# Processor_Interface.net
KiCad netlist of a schematic drawn in EAGLE
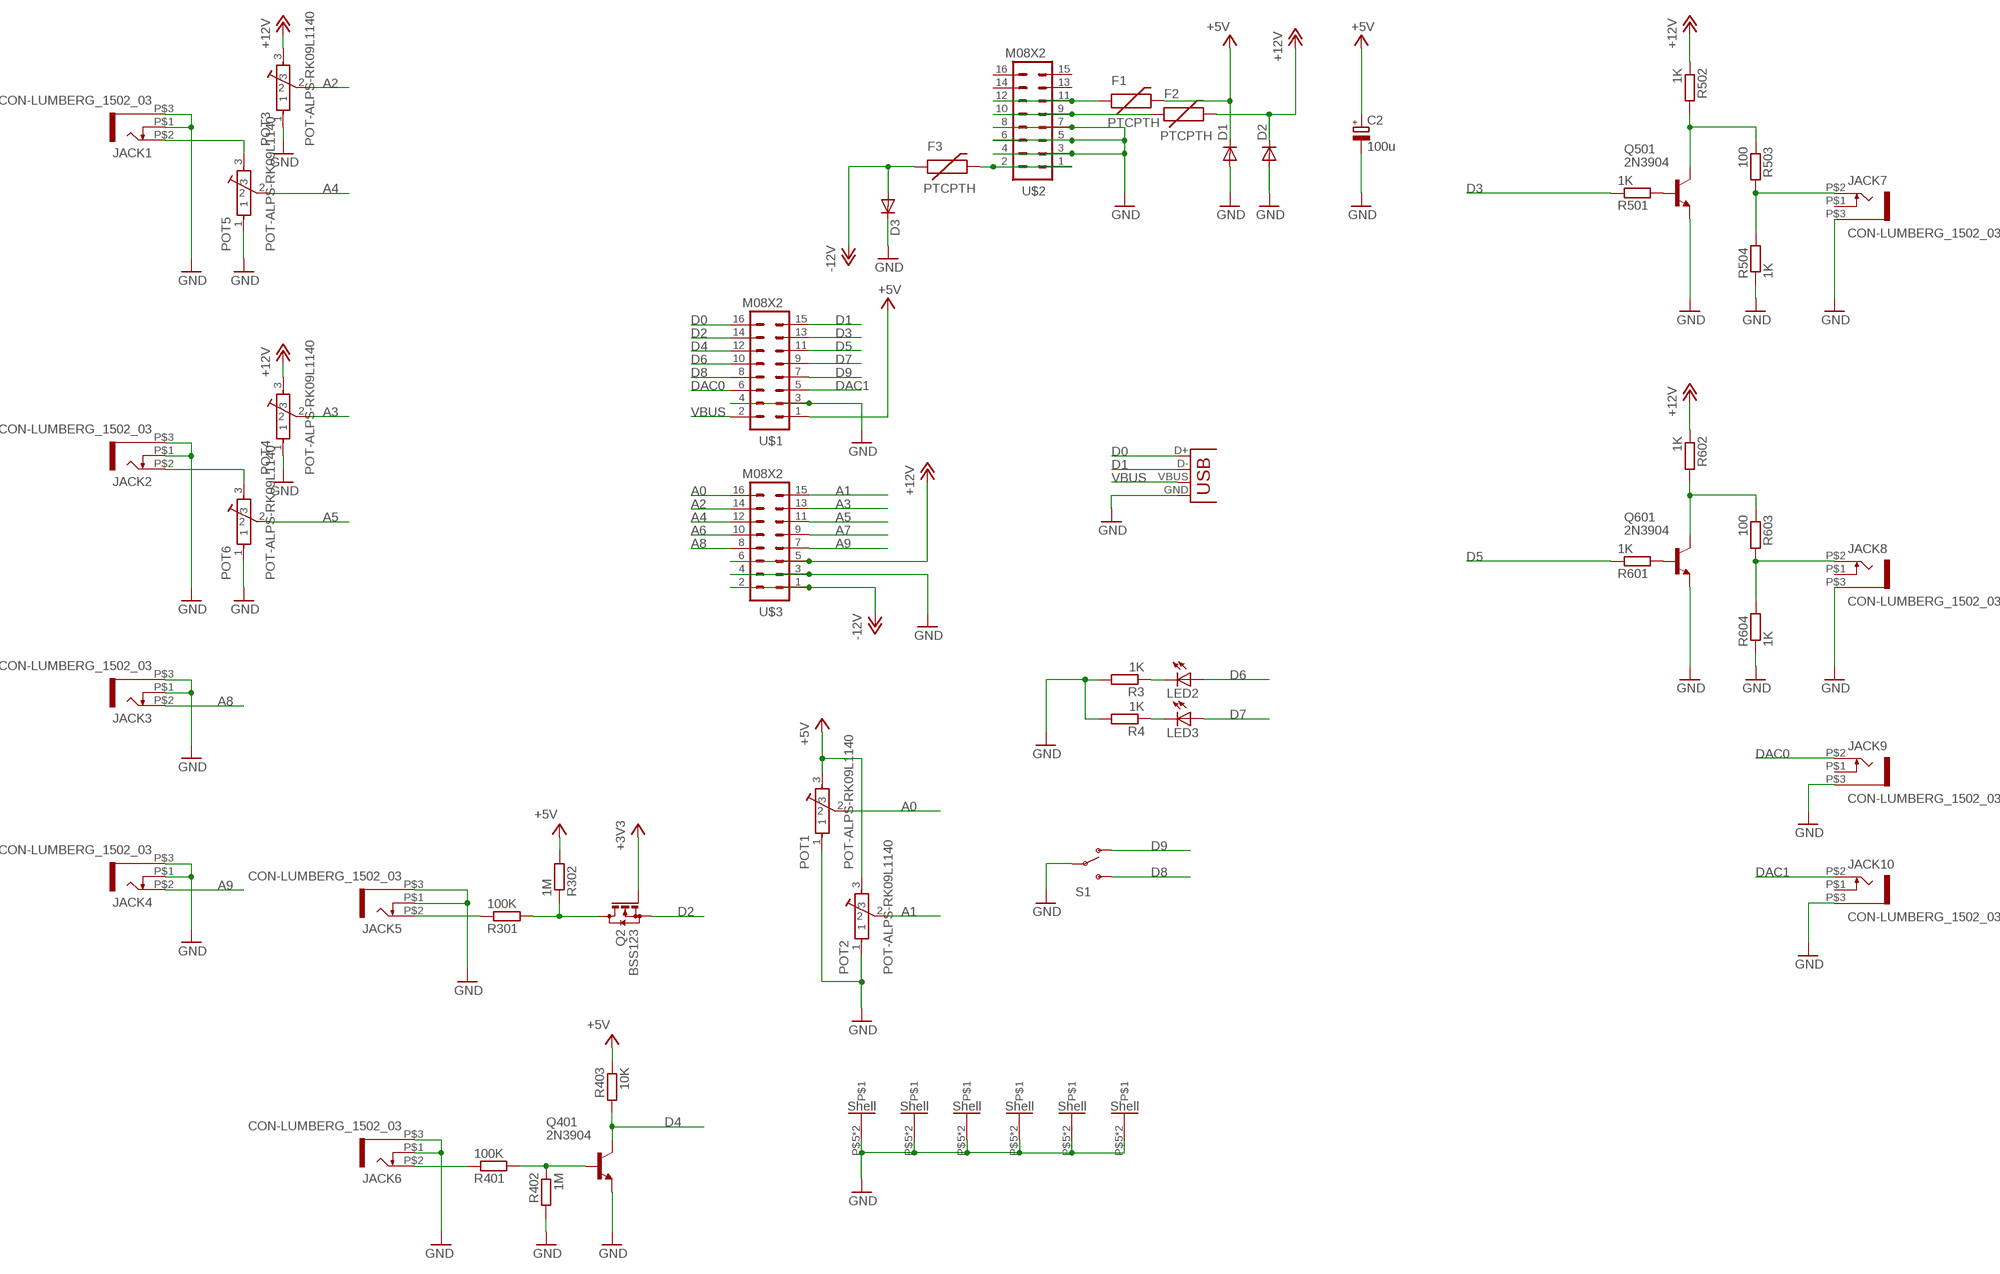
[diagram p0: schematic, sheet 1]

(export (version "E")
  (design (tool "Eeschema 10.0.6"))
  (components
    (comp (ref "C2")
      (value "100u")
      (footprint "eagle-import:E5-6")
      (libsource (lib "eagle-import") (part "CPOL-EUE5-6"))
    )
    (comp (ref "D1")
      (value "DIODEPTH")
      (footprint "eagle-import:DIODE-1N4001")
      (libsource (lib "eagle-import") (part "DIODEPTH"))
    )
    (comp (ref "D2")
      (value "DIODEPTH")
      (footprint "eagle-import:DIODE-1N4001")
      (libsource (lib "eagle-import") (part "DIODEPTH"))
    )
    (comp (ref "D3")
      (value "DIODEPTH")
      (footprint "eagle-import:DIODE-1N4001")
      (libsource (lib "eagle-import") (part "DIODEPTH"))
    )
    (comp (ref "F1")
      (value "PTCPTH")
      (footprint "eagle-import:PTC")
      (libsource (lib "eagle-import") (part "PTCPTH"))
    )
    (comp (ref "F2")
      (value "PTCPTH")
      (footprint "eagle-import:PTC")
      (libsource (lib "eagle-import") (part "PTCPTH"))
    )
    (comp (ref "F3")
      (value "PTCPTH")
      (footprint "eagle-import:PTC")
      (libsource (lib "eagle-import") (part "PTCPTH"))
    )
    (comp (ref "JACK1")
      (value "CON-LUMBERG_1502_03")
      (footprint "eagle-import:CON-LUMBERG_1502_03")
      (libsource (lib "eagle-import") (part "CON-LUMBERG_1502_03"))
    )
    (comp (ref "JACK2")
      (value "CON-LUMBERG_1502_03")
      (footprint "eagle-import:CON-LUMBERG_1502_03")
      (libsource (lib "eagle-import") (part "CON-LUMBERG_1502_03"))
    )
    (comp (ref "JACK3")
      (value "CON-LUMBERG_1502_03")
      (footprint "eagle-import:CON-LUMBERG_1502_03")
      (libsource (lib "eagle-import") (part "CON-LUMBERG_1502_03"))
    )
    (comp (ref "JACK4")
      (value "CON-LUMBERG_1502_03")
      (footprint "eagle-import:CON-LUMBERG_1502_03")
      (libsource (lib "eagle-import") (part "CON-LUMBERG_1502_03"))
    )
    (comp (ref "JACK5")
      (value "CON-LUMBERG_1502_03")
      (footprint "eagle-import:CON-LUMBERG_1502_03")
      (libsource (lib "eagle-import") (part "CON-LUMBERG_1502_03"))
    )
    (comp (ref "JACK6")
      (value "CON-LUMBERG_1502_03")
      (footprint "eagle-import:CON-LUMBERG_1502_03")
      (libsource (lib "eagle-import") (part "CON-LUMBERG_1502_03"))
    )
    (comp (ref "JACK7")
      (value "CON-LUMBERG_1502_03")
      (footprint "eagle-import:CON-LUMBERG_1502_03")
      (libsource (lib "eagle-import") (part "CON-LUMBERG_1502_03"))
    )
    (comp (ref "JACK8")
      (value "CON-LUMBERG_1502_03")
      (footprint "eagle-import:CON-LUMBERG_1502_03")
      (libsource (lib "eagle-import") (part "CON-LUMBERG_1502_03"))
    )
    (comp (ref "JACK9")
      (value "CON-LUMBERG_1502_03")
      (footprint "eagle-import:CON-LUMBERG_1502_03")
      (libsource (lib "eagle-import") (part "CON-LUMBERG_1502_03"))
    )
    (comp (ref "JACK10")
      (value "CON-LUMBERG_1502_03")
      (footprint "eagle-import:CON-LUMBERG_1502_03")
      (libsource (lib "eagle-import") (part "CON-LUMBERG_1502_03"))
    )
    (comp (ref "LED2")
      (value "LED3MM")
      (footprint "eagle-import:LED3MM")
      (libsource (lib "eagle-import") (part "LED3MM"))
    )
    (comp (ref "LED3")
      (value "LED3MM")
      (footprint "eagle-import:LED3MM")
      (libsource (lib "eagle-import") (part "LED3MM"))
    )
    (comp (ref "POT1")
      (value "POT-ALPS-RK09L1140")
      (footprint "eagle-import:POT-ALPS-RK09L1140")
      (libsource (lib "eagle-import") (part "POT-ALPS-RK09L1140"))
    )
    (comp (ref "POT2")
      (value "POT-ALPS-RK09L1140")
      (footprint "eagle-import:POT-ALPS-RK09L1140")
      (libsource (lib "eagle-import") (part "POT-ALPS-RK09L1140"))
    )
    (comp (ref "POT3")
      (value "POT-ALPS-RK09L1140")
      (footprint "eagle-import:POT-ALPS-RK09L1140")
      (libsource (lib "eagle-import") (part "POT-ALPS-RK09L1140"))
    )
    (comp (ref "POT4")
      (value "POT-ALPS-RK09L1140")
      (footprint "eagle-import:POT-ALPS-RK09L1140")
      (libsource (lib "eagle-import") (part "POT-ALPS-RK09L1140"))
    )
    (comp (ref "POT5")
      (value "POT-ALPS-RK09L1140")
      (footprint "eagle-import:POT-ALPS-RK09L1140")
      (libsource (lib "eagle-import") (part "POT-ALPS-RK09L1140"))
    )
    (comp (ref "POT6")
      (value "POT-ALPS-RK09L1140")
      (footprint "eagle-import:POT-ALPS-RK09L1140")
      (libsource (lib "eagle-import") (part "POT-ALPS-RK09L1140"))
    )
    (comp (ref "Q2")
      (value "BSS123")
      (footprint "eagle-import:SOT23")
      (libsource (lib "eagle-import") (part "BSS123"))
    )
    (comp (ref "Q401")
      (value "2N3904")
      (footprint "eagle-import:TO92")
      (libsource (lib "eagle-import") (part "2N3904"))
    )
    (comp (ref "Q501")
      (value "2N3904")
      (footprint "eagle-import:TO92")
      (libsource (lib "eagle-import") (part "2N3904"))
    )
    (comp (ref "Q601")
      (value "2N3904")
      (footprint "eagle-import:TO92")
      (libsource (lib "eagle-import") (part "2N3904"))
    )
    (comp (ref "R3")
      (value "1K")
      (footprint "eagle-import:0204_7")
      (libsource (lib "eagle-import") (part "R-EU_0204/7"))
    )
    (comp (ref "R4")
      (value "1K")
      (footprint "eagle-import:0204_7")
      (libsource (lib "eagle-import") (part "R-EU_0204/7"))
    )
    (comp (ref "R301")
      (value "100K")
      (footprint "eagle-import:0204_7")
      (libsource (lib "eagle-import") (part "R-EU_0204/7"))
    )
    (comp (ref "R302")
      (value "1M")
      (footprint "eagle-import:0204_7")
      (libsource (lib "eagle-import") (part "R-EU_0204/7"))
    )
    (comp (ref "R401")
      (value "100K")
      (footprint "eagle-import:0204_7")
      (libsource (lib "eagle-import") (part "R-EU_0204/7"))
    )
    (comp (ref "R402")
      (value "1M")
      (footprint "eagle-import:0204_7")
      (libsource (lib "eagle-import") (part "R-EU_0204/7"))
    )
    (comp (ref "R403")
      (value "10K")
      (footprint "eagle-import:0204_7")
      (libsource (lib "eagle-import") (part "R-EU_0204/7"))
    )
    (comp (ref "R501")
      (value "1K")
      (footprint "eagle-import:0204_7")
      (libsource (lib "eagle-import") (part "R-EU_0204/7"))
    )
    (comp (ref "R502")
      (value "1K")
      (footprint "eagle-import:0204_7")
      (libsource (lib "eagle-import") (part "R-EU_0204/7"))
    )
    (comp (ref "R503")
      (value "100")
      (footprint "eagle-import:0204_7")
      (libsource (lib "eagle-import") (part "R-EU_0204/7"))
    )
    (comp (ref "R504")
      (value "1K")
      (footprint "eagle-import:0204_7")
      (libsource (lib "eagle-import") (part "R-EU_0204/7"))
    )
    (comp (ref "R601")
      (value "1K")
      (footprint "eagle-import:0204_7")
      (libsource (lib "eagle-import") (part "R-EU_0204/7"))
    )
    (comp (ref "R602")
      (value "1K")
      (footprint "eagle-import:0204_7")
      (libsource (lib "eagle-import") (part "R-EU_0204/7"))
    )
    (comp (ref "R603")
      (value "100")
      (footprint "eagle-import:0204_7")
      (libsource (lib "eagle-import") (part "R-EU_0204/7"))
    )
    (comp (ref "R604")
      (value "1K")
      (footprint "eagle-import:0204_7")
      (libsource (lib "eagle-import") (part "R-EU_0204/7"))
    )
    (comp (ref "S1")
      (value "SWITCH-SPST")
      (footprint "eagle-import:SWITCH-SPDT-SALECOM-T8014")
      (libsource (lib "eagle-import") (part "SWITCH-SPST"))
    )
    (comp (ref "U$1")
      (value "M08X2")
      (footprint "eagle-import:2X8")
      (libsource (lib "eagle-import") (part "M08X2"))
    )
    (comp (ref "U$2")
      (value "M08X2")
      (footprint "eagle-import:2X8")
      (libsource (lib "eagle-import") (part "M08X2"))
    )
    (comp (ref "U$3")
      (value "M08X2")
      (footprint "eagle-import:2X8")
      (libsource (lib "eagle-import") (part "M08X2"))
    )
    (comp (ref "X1")
      (value "USBPTH-VERTICAL")
      (footprint "eagle-import:USB-B-PTH-VERTICAL")
      (libsource (lib "eagle-import") (part "USBPTH-VERTICAL"))
    )
  )
  (nets
    (net (code "1") (name "+3V3") (class "Default")
      (node (ref "Q2") (pin "1") (pinfunction "G_1") (pintype "passive"))
    )
    (net (code "2") (name "+5V") (class "Default")
      (node (ref "C2") (pin "+") (pinfunction "+_+") (pintype "passive"))
      (node (ref "D1") (pin "C") (pinfunction "C_C") (pintype "passive"))
      (node (ref "F1") (pin "P$2") (pinfunction "2_P$2") (pintype "bidirectional"))
      (node (ref "POT1") (pin "3") (pinfunction "3_3") (pintype "bidirectional"))
      (node (ref "POT2") (pin "3") (pinfunction "3_3") (pintype "bidirectional"))
      (node (ref "R302") (pin "2") (pinfunction "2_2") (pintype "passive"))
      (node (ref "R403") (pin "1") (pinfunction "1_1") (pintype "passive"))
      (node (ref "U$1") (pin "1") (pinfunction "1_1") (pintype "passive"))
    )
    (net (code "3") (name "+12V") (class "Default")
      (node (ref "D2") (pin "C") (pinfunction "C_C") (pintype "passive"))
      (node (ref "F2") (pin "P$2") (pinfunction "2_P$2") (pintype "bidirectional"))
      (node (ref "POT3") (pin "3") (pinfunction "3_3") (pintype "bidirectional"))
      (node (ref "POT4") (pin "3") (pinfunction "3_3") (pintype "bidirectional"))
      (node (ref "R502") (pin "1") (pinfunction "1_1") (pintype "passive"))
      (node (ref "R602") (pin "1") (pinfunction "1_1") (pintype "passive"))
      (node (ref "U$3") (pin "5") (pinfunction "5_5") (pintype "passive"))
      (node (ref "U$3") (pin "6") (pinfunction "6_6") (pintype "passive"))
    )
    (net (code "4") (name "-12V") (class "Default")
      (node (ref "D3") (pin "A") (pinfunction "A_A") (pintype "passive"))
      (node (ref "F3") (pin "P$1") (pinfunction "1_P$1") (pintype "bidirectional"))
      (node (ref "U$3") (pin "1") (pinfunction "1_1") (pintype "passive"))
      (node (ref "U$3") (pin "2") (pinfunction "2_2") (pintype "passive"))
    )
    (net (code "5") (name "/A0") (class "Default")
      (node (ref "POT1") (pin "2") (pinfunction "2_2") (pintype "bidirectional"))
      (node (ref "U$3") (pin "16") (pinfunction "16_16") (pintype "passive"))
    )
    (net (code "6") (name "/A1") (class "Default")
      (node (ref "POT2") (pin "2") (pinfunction "2_2") (pintype "bidirectional"))
      (node (ref "U$3") (pin "15") (pinfunction "15_15") (pintype "passive"))
    )
    (net (code "7") (name "/A2") (class "Default")
      (node (ref "POT3") (pin "2") (pinfunction "2_2") (pintype "bidirectional"))
      (node (ref "U$3") (pin "14") (pinfunction "14_14") (pintype "passive"))
    )
    (net (code "8") (name "/A3") (class "Default")
      (node (ref "POT4") (pin "2") (pinfunction "2_2") (pintype "bidirectional"))
      (node (ref "U$3") (pin "13") (pinfunction "13_13") (pintype "passive"))
    )
    (net (code "9") (name "/A4") (class "Default")
      (node (ref "POT5") (pin "2") (pinfunction "2_2") (pintype "bidirectional"))
      (node (ref "U$3") (pin "12") (pinfunction "12_12") (pintype "passive"))
    )
    (net (code "10") (name "/A5") (class "Default")
      (node (ref "POT6") (pin "2") (pinfunction "2_2") (pintype "bidirectional"))
      (node (ref "U$3") (pin "11") (pinfunction "11_11") (pintype "passive"))
    )
    (net (code "11") (name "/A6") (class "Default")
      (node (ref "U$3") (pin "10") (pinfunction "10_10") (pintype "passive"))
    )
    (net (code "12") (name "/A7") (class "Default")
      (node (ref "U$3") (pin "9") (pinfunction "9_9") (pintype "passive"))
    )
    (net (code "13") (name "/A8") (class "Default")
      (node (ref "JACK3") (pin "P$2") (pinfunction "3_P$2") (pintype "passive"))
      (node (ref "U$3") (pin "8") (pinfunction "8_8") (pintype "passive"))
    )
    (net (code "14") (name "/A9") (class "Default")
      (node (ref "JACK4") (pin "P$2") (pinfunction "3_P$2") (pintype "passive"))
      (node (ref "U$3") (pin "7") (pinfunction "7_7") (pintype "passive"))
    )
    (net (code "15") (name "/D0") (class "Default")
      (node (ref "U$1") (pin "16") (pinfunction "16_16") (pintype "passive"))
      (node (ref "X1") (pin "D+") (pinfunction "D+_D+") (pintype "bidirectional"))
    )
    (net (code "16") (name "/D1") (class "Default")
      (node (ref "U$1") (pin "15") (pinfunction "15_15") (pintype "passive"))
      (node (ref "X1") (pin "D-") (pinfunction "D-_D-") (pintype "bidirectional"))
    )
    (net (code "17") (name "/D2") (class "Default")
      (node (ref "Q2") (pin "2") (pinfunction "S_2") (pintype "passive"))
      (node (ref "U$1") (pin "14") (pinfunction "14_14") (pintype "passive"))
    )
    (net (code "18") (name "/D3") (class "Default")
      (node (ref "R501") (pin "1") (pinfunction "1_1") (pintype "passive"))
      (node (ref "U$1") (pin "13") (pinfunction "13_13") (pintype "passive"))
    )
    (net (code "19") (name "/D4") (class "Default")
      (node (ref "Q401") (pin "1") (pinfunction "C_1") (pintype "passive"))
      (node (ref "R403") (pin "2") (pinfunction "2_2") (pintype "passive"))
      (node (ref "U$1") (pin "12") (pinfunction "12_12") (pintype "passive"))
    )
    (net (code "20") (name "/D5") (class "Default")
      (node (ref "R601") (pin "1") (pinfunction "1_1") (pintype "passive"))
      (node (ref "U$1") (pin "11") (pinfunction "11_11") (pintype "passive"))
    )
    (net (code "21") (name "/D6") (class "Default")
      (node (ref "LED2") (pin "A") (pinfunction "A_A") (pintype "passive"))
      (node (ref "U$1") (pin "10") (pinfunction "10_10") (pintype "passive"))
    )
    (net (code "22") (name "/D7") (class "Default")
      (node (ref "LED3") (pin "A") (pinfunction "A_A") (pintype "passive"))
      (node (ref "U$1") (pin "9") (pinfunction "9_9") (pintype "passive"))
    )
    (net (code "23") (name "/D8") (class "Default")
      (node (ref "S1") (pin "3") (pinfunction "S_3") (pintype "passive"))
      (node (ref "U$1") (pin "8") (pinfunction "8_8") (pintype "passive"))
    )
    (net (code "24") (name "/D9") (class "Default")
      (node (ref "S1") (pin "1") (pinfunction "O_1") (pintype "passive"))
      (node (ref "U$1") (pin "7") (pinfunction "7_7") (pintype "passive"))
    )
    (net (code "25") (name "/DAC0") (class "Default")
      (node (ref "JACK9") (pin "P$2") (pinfunction "3_P$2") (pintype "passive"))
      (node (ref "U$1") (pin "6") (pinfunction "6_6") (pintype "passive"))
    )
    (net (code "26") (name "/DAC1") (class "Default")
      (node (ref "JACK10") (pin "P$2") (pinfunction "3_P$2") (pintype "passive"))
      (node (ref "U$1") (pin "5") (pinfunction "5_5") (pintype "passive"))
    )
    (net (code "27") (name "/VBUS") (class "Default")
      (node (ref "U$1") (pin "2") (pinfunction "2_2") (pintype "passive"))
      (node (ref "X1") (pin "VBUS") (pinfunction "VBUS_VBUS") (pintype "bidirectional"))
    )
    (net (code "28") (name "GND") (class "Default")
      (node (ref "C2") (pin "-") (pinfunction "-_-") (pintype "passive"))
      (node (ref "D1") (pin "A") (pinfunction "A_A") (pintype "passive"))
      (node (ref "D2") (pin "A") (pinfunction "A_A") (pintype "passive"))
      (node (ref "D3") (pin "C") (pinfunction "C_C") (pintype "passive"))
      (node (ref "JACK1") (pin "P$1") (pinfunction "4_P$1") (pintype "passive"))
      (node (ref "JACK1") (pin "P$3") (pinfunction "5_P$3") (pintype "passive"))
      (node (ref "JACK10") (pin "P$3") (pinfunction "5_P$3") (pintype "passive"))
      (node (ref "JACK2") (pin "P$1") (pinfunction "4_P$1") (pintype "passive"))
      (node (ref "JACK2") (pin "P$3") (pinfunction "5_P$3") (pintype "passive"))
      (node (ref "JACK3") (pin "P$1") (pinfunction "4_P$1") (pintype "passive"))
      (node (ref "JACK3") (pin "P$3") (pinfunction "5_P$3") (pintype "passive"))
      (node (ref "JACK4") (pin "P$1") (pinfunction "4_P$1") (pintype "passive"))
      (node (ref "JACK4") (pin "P$3") (pinfunction "5_P$3") (pintype "passive"))
      (node (ref "JACK5") (pin "P$1") (pinfunction "4_P$1") (pintype "passive"))
      (node (ref "JACK5") (pin "P$3") (pinfunction "5_P$3") (pintype "passive"))
      (node (ref "JACK6") (pin "P$1") (pinfunction "4_P$1") (pintype "passive"))
      (node (ref "JACK6") (pin "P$3") (pinfunction "5_P$3") (pintype "passive"))
      (node (ref "JACK7") (pin "P$3") (pinfunction "5_P$3") (pintype "passive"))
      (node (ref "JACK8") (pin "P$3") (pinfunction "5_P$3") (pintype "passive"))
      (node (ref "JACK9") (pin "P$3") (pinfunction "5_P$3") (pintype "passive"))
      (node (ref "POT1") (pin "1") (pinfunction "1_1") (pintype "bidirectional"))
      (node (ref "POT1") (pin "P$5") (pinfunction "P$1_P$5") (pintype "bidirectional"))
      (node (ref "POT1") (pin "P$6") (pinfunction "P$1_P$6") (pintype "bidirectional"))
      (node (ref "POT2") (pin "1") (pinfunction "1_1") (pintype "bidirectional"))
      (node (ref "POT2") (pin "P$5") (pinfunction "P$1_P$5") (pintype "bidirectional"))
      (node (ref "POT2") (pin "P$6") (pinfunction "P$1_P$6") (pintype "bidirectional"))
      (node (ref "POT3") (pin "1") (pinfunction "1_1") (pintype "bidirectional"))
      (node (ref "POT3") (pin "P$5") (pinfunction "P$1_P$5") (pintype "bidirectional"))
      (node (ref "POT3") (pin "P$6") (pinfunction "P$1_P$6") (pintype "bidirectional"))
      (node (ref "POT4") (pin "1") (pinfunction "1_1") (pintype "bidirectional"))
      (node (ref "POT4") (pin "P$5") (pinfunction "P$1_P$5") (pintype "bidirectional"))
      (node (ref "POT4") (pin "P$6") (pinfunction "P$1_P$6") (pintype "bidirectional"))
      (node (ref "POT5") (pin "1") (pinfunction "1_1") (pintype "bidirectional"))
      (node (ref "POT5") (pin "P$5") (pinfunction "P$1_P$5") (pintype "bidirectional"))
      (node (ref "POT5") (pin "P$6") (pinfunction "P$1_P$6") (pintype "bidirectional"))
      (node (ref "POT6") (pin "1") (pinfunction "1_1") (pintype "bidirectional"))
      (node (ref "POT6") (pin "P$5") (pinfunction "P$1_P$5") (pintype "bidirectional"))
      (node (ref "POT6") (pin "P$6") (pinfunction "P$1_P$6") (pintype "bidirectional"))
      (node (ref "Q401") (pin "3") (pinfunction "E_3") (pintype "passive"))
      (node (ref "Q501") (pin "3") (pinfunction "E_3") (pintype "passive"))
      (node (ref "Q601") (pin "3") (pinfunction "E_3") (pintype "passive"))
      (node (ref "R3") (pin "2") (pinfunction "2_2") (pintype "passive"))
      (node (ref "R4") (pin "2") (pinfunction "2_2") (pintype "passive"))
      (node (ref "R402") (pin "2") (pinfunction "2_2") (pintype "passive"))
      (node (ref "R504") (pin "1") (pinfunction "1_1") (pintype "passive"))
      (node (ref "R604") (pin "1") (pinfunction "1_1") (pintype "passive"))
      (node (ref "S1") (pin "2") (pinfunction "P_2") (pintype "passive"))
      (node (ref "U$1") (pin "3") (pinfunction "3_3") (pintype "passive"))
      (node (ref "U$1") (pin "4") (pinfunction "4_4") (pintype "passive"))
      (node (ref "U$2") (pin "3") (pinfunction "3_3") (pintype "passive"))
      (node (ref "U$2") (pin "4") (pinfunction "4_4") (pintype "passive"))
      (node (ref "U$2") (pin "5") (pinfunction "5_5") (pintype "passive"))
      (node (ref "U$2") (pin "6") (pinfunction "6_6") (pintype "passive"))
      (node (ref "U$2") (pin "7") (pinfunction "7_7") (pintype "passive"))
      (node (ref "U$2") (pin "8") (pinfunction "8_8") (pintype "passive"))
      (node (ref "U$3") (pin "3") (pinfunction "3_3") (pintype "passive"))
      (node (ref "U$3") (pin "4") (pinfunction "4_4") (pintype "passive"))
      (node (ref "X1") (pin "GND") (pinfunction "GND_GND") (pintype "bidirectional"))
    )
    (net (code "29") (name "Net-(F1-1)") (class "Default")
      (node (ref "F1") (pin "P$1") (pinfunction "1_P$1") (pintype "bidirectional"))
      (node (ref "U$2") (pin "11") (pinfunction "11_11") (pintype "passive"))
      (node (ref "U$2") (pin "12") (pinfunction "12_12") (pintype "passive"))
    )
    (net (code "30") (name "Net-(F2-1)") (class "Default")
      (node (ref "F2") (pin "P$1") (pinfunction "1_P$1") (pintype "bidirectional"))
      (node (ref "U$2") (pin "10") (pinfunction "10_10") (pintype "passive"))
      (node (ref "U$2") (pin "9") (pinfunction "9_9") (pintype "passive"))
    )
    (net (code "31") (name "Net-(F3-2)") (class "Default")
      (node (ref "F3") (pin "P$2") (pinfunction "2_P$2") (pintype "bidirectional"))
      (node (ref "U$2") (pin "1") (pinfunction "1_1") (pintype "passive"))
      (node (ref "U$2") (pin "2") (pinfunction "2_2") (pintype "passive"))
    )
    (net (code "32") (name "Net-(JACK1-3)") (class "Default")
      (node (ref "JACK1") (pin "P$2") (pinfunction "3_P$2") (pintype "passive"))
      (node (ref "POT5") (pin "3") (pinfunction "3_3") (pintype "bidirectional"))
    )
    (net (code "33") (name "Net-(JACK2-3)") (class "Default")
      (node (ref "JACK2") (pin "P$2") (pinfunction "3_P$2") (pintype "passive"))
      (node (ref "POT6") (pin "3") (pinfunction "3_3") (pintype "bidirectional"))
    )
    (net (code "34") (name "Net-(JACK5-3)") (class "Default")
      (node (ref "JACK5") (pin "P$2") (pinfunction "3_P$2") (pintype "passive"))
      (node (ref "R301") (pin "1") (pinfunction "1_1") (pintype "passive"))
    )
    (net (code "35") (name "Net-(JACK6-3)") (class "Default")
      (node (ref "JACK6") (pin "P$2") (pinfunction "3_P$2") (pintype "passive"))
      (node (ref "R401") (pin "1") (pinfunction "1_1") (pintype "passive"))
    )
    (net (code "36") (name "Net-(JACK7-3)") (class "Default")
      (node (ref "JACK7") (pin "P$2") (pinfunction "3_P$2") (pintype "passive"))
      (node (ref "R503") (pin "2") (pinfunction "2_2") (pintype "passive"))
      (node (ref "R504") (pin "2") (pinfunction "2_2") (pintype "passive"))
    )
    (net (code "37") (name "Net-(JACK8-3)") (class "Default")
      (node (ref "JACK8") (pin "P$2") (pinfunction "3_P$2") (pintype "passive"))
      (node (ref "R603") (pin "2") (pinfunction "2_2") (pintype "passive"))
      (node (ref "R604") (pin "2") (pinfunction "2_2") (pintype "passive"))
    )
    (net (code "38") (name "Net-(LED2-C)") (class "Default")
      (node (ref "LED2") (pin "K") (pinfunction "C_K") (pintype "passive"))
      (node (ref "R3") (pin "1") (pinfunction "1_1") (pintype "passive"))
    )
    (net (code "39") (name "Net-(LED3-C)") (class "Default")
      (node (ref "LED3") (pin "K") (pinfunction "C_K") (pintype "passive"))
      (node (ref "R4") (pin "1") (pinfunction "1_1") (pintype "passive"))
    )
    (net (code "40") (name "Net-(Q2-D)") (class "Default")
      (node (ref "Q2") (pin "3") (pinfunction "D_3") (pintype "passive"))
      (node (ref "R301") (pin "2") (pinfunction "2_2") (pintype "passive"))
      (node (ref "R302") (pin "1") (pinfunction "1_1") (pintype "passive"))
    )
    (net (code "41") (name "Net-(Q401-B)") (class "Default")
      (node (ref "Q401") (pin "2") (pinfunction "B_2") (pintype "passive"))
      (node (ref "R401") (pin "2") (pinfunction "2_2") (pintype "passive"))
      (node (ref "R402") (pin "1") (pinfunction "1_1") (pintype "passive"))
    )
    (net (code "42") (name "Net-(Q501-B)") (class "Default")
      (node (ref "Q501") (pin "2") (pinfunction "B_2") (pintype "passive"))
      (node (ref "R501") (pin "2") (pinfunction "2_2") (pintype "passive"))
    )
    (net (code "43") (name "Net-(Q501-C)") (class "Default")
      (node (ref "Q501") (pin "1") (pinfunction "C_1") (pintype "passive"))
      (node (ref "R502") (pin "2") (pinfunction "2_2") (pintype "passive"))
      (node (ref "R503") (pin "1") (pinfunction "1_1") (pintype "passive"))
    )
    (net (code "44") (name "Net-(Q601-B)") (class "Default")
      (node (ref "Q601") (pin "2") (pinfunction "B_2") (pintype "passive"))
      (node (ref "R601") (pin "2") (pinfunction "2_2") (pintype "passive"))
    )
    (net (code "45") (name "Net-(Q601-C)") (class "Default")
      (node (ref "Q601") (pin "1") (pinfunction "C_1") (pintype "passive"))
      (node (ref "R602") (pin "2") (pinfunction "2_2") (pintype "passive"))
      (node (ref "R603") (pin "1") (pinfunction "1_1") (pintype "passive"))
    )
    (net (code "46") (name "unconnected-(JACK7-4-PadP$1)") (class "Default")
      (node (ref "JACK7") (pin "P$1") (pinfunction "4_P$1") (pintype "passive"))
    )
    (net (code "47") (name "unconnected-(JACK8-4-PadP$1)") (class "Default")
      (node (ref "JACK8") (pin "P$1") (pinfunction "4_P$1") (pintype "passive"))
    )
    (net (code "48") (name "unconnected-(JACK9-4-PadP$1)") (class "Default")
      (node (ref "JACK9") (pin "P$1") (pinfunction "4_P$1") (pintype "passive"))
    )
    (net (code "49") (name "unconnected-(JACK10-4-PadP$1)") (class "Default")
      (node (ref "JACK10") (pin "P$1") (pinfunction "4_P$1") (pintype "passive"))
    )
    (net (code "50") (name "unconnected-(U$2-Pad13)") (class "Default")
      (node (ref "U$2") (pin "13") (pinfunction "13_13") (pintype "passive"))
    )
    (net (code "51") (name "unconnected-(U$2-Pad14)") (class "Default")
      (node (ref "U$2") (pin "14") (pinfunction "14_14") (pintype "passive"))
    )
    (net (code "52") (name "unconnected-(U$2-Pad15)") (class "Default")
      (node (ref "U$2") (pin "15") (pinfunction "15_15") (pintype "passive"))
    )
    (net (code "53") (name "unconnected-(U$2-Pad16)") (class "Default")
      (node (ref "U$2") (pin "16") (pinfunction "16_16") (pintype "passive"))
    )
  )
)
